# POWER.net
KiCad netlist of a schematic drawn in Altium Designer
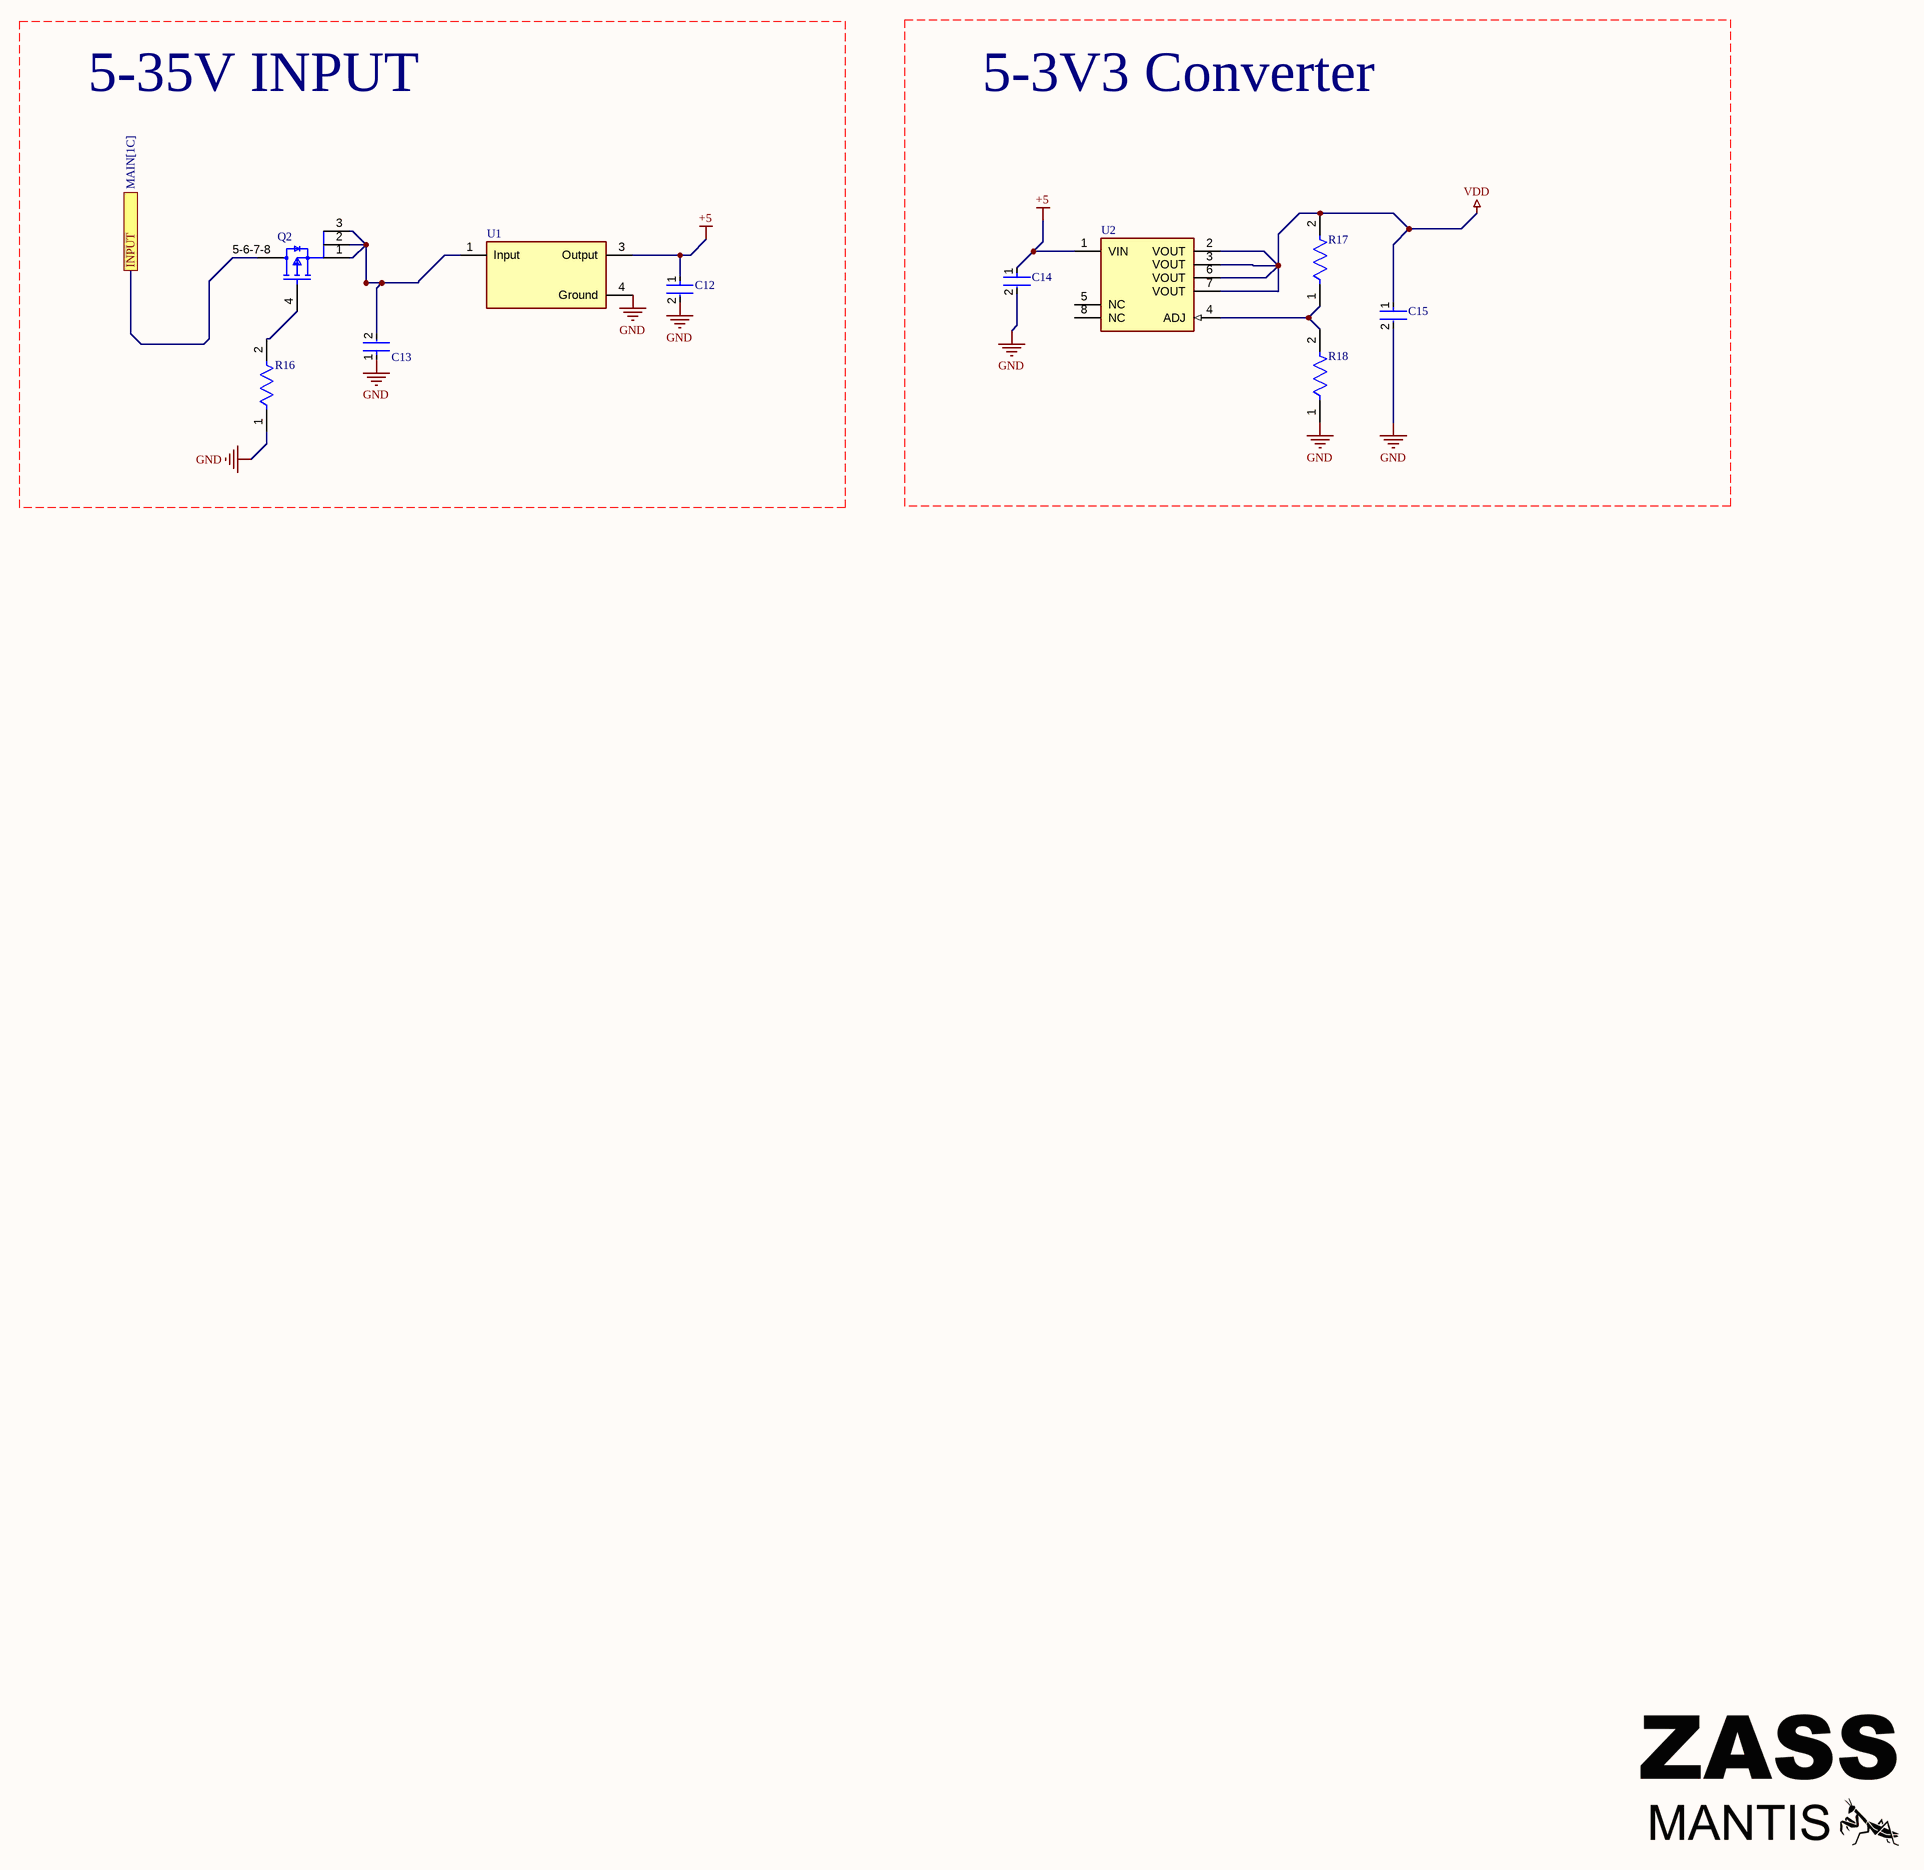
[diagram p0: POWER.SchDoc]

(export (version "E")
  (design (tool "Eeschema 10.0.6"))
  (components
    (comp (ref "C12")
      (value "CC0805KRX7R5BB104")
      (footprint "FP-CC0805-EA-MFG")
      (description "CAP CER X7R 0805")
      (libsource (lib "Altium Content Vault") (part "b4654b650e69147ec39a6b967a45e02"))
    )
    (comp (ref "C13")
      (value "C0805C104K5RACTU")
      (footprint "FP-C0805C-DN-MFG")
      (description "CAP CER 0.1UF 50V X7R 0805")
      (fields
        (field (name "MANUFACTURER") "KEMET")
        (field (name "OCTOPART") "https://octopart.com/c0805c104k5ractu-kemet-143926")
      )
      (libsource (lib "Altium Content Vault") (part "b4654b650e69147ec39a6b967a45e02"))
    )
    (comp (ref "C14")
      (value "CC0805KRX7R5BB104")
      (footprint "FP-CC0805-EA-MFG")
      (description "CAP CER X7R 0805")
      (libsource (lib "Altium Content Vault") (part "b4654b650e69147ec39a6b967a45e02"))
    )
    (comp (ref "C15")
      (value "CC0805KRX7R5BB104")
      (footprint "FP-CC0805-EA-MFG")
      (description "CAP CER X7R 0805")
      (libsource (lib "Altium Content Vault") (part "b4654b650e69147ec39a6b967a45e02"))
    )
    (comp (ref "Q2")
      (value "SI7113ADN-T1-GE3")
      (footprint "FP-S16-2667-SINGLE-MFG")
      (description "MOSFET P-CH 100V 10.8A 1212-8")
      (fields
        (field (name "MANUFACTURER") "Vishay")
        (field (name "OCTOPART") "https://octopart.com/si7113adn-t1-ge3-vishay-88182558")
      )
      (libsource (lib "Altium Content Vault") (part "a2b2833ae26e75c929b926ecaf5219e"))
    )
    (comp (ref "R16")
      (value "CRGCQ0603F1K2")
      (footprint "FP-CRGCQ0603-IPC_C")
      (description "CRGCQ 0603 1K2 1%")
      (fields
        (field (name "OCTOPART") "https://octopart.com/crgcq0603f1k2-te+connectivity-91018051")
        (field (name "MANUFACTURER") "TE Connectivity")
      )
      (libsource (lib "Altium Content Vault") (part "1029c3af85768c4190bb7ad29bc67b5"))
    )
    (comp (ref "R17")
      (value "CRGCQ0603F1K2")
      (footprint "FP-CRGCQ0603-IPC_C")
      (description "CRGCQ 0603 1K2 1%")
      (fields
        (field (name "OCTOPART") "https://octopart.com/crgcq0603f1k2-te+connectivity-91018051")
        (field (name "MANUFACTURER") "TE Connectivity")
      )
      (libsource (lib "Altium Content Vault") (part "1029c3af85768c4190bb7ad29bc67b5"))
    )
    (comp (ref "R18")
      (value "RC3216J202CS")
      (footprint "FP-RC3216-IPC_A")
      (description "Res Thick Film 1206 2kΩ 5% 0.25W ±100ppm/°C Molded SMD T/R")
      (fields (field (name "TOLERANCE") "5%"))
      (libsource (lib "Altium Content Vault") (part "1029c3af85768c4190bb7ad29bc67b5"))
    )
    (comp (ref "U1")
      (value "MC7805CDTRKG")
      (footprint "FP-369C-MFG")
      (description "IC REG LINEAR 5V 1A DPAK")
      (libsource (lib "Altium Content Vault") (part "10ca12a7ef27ecffb14ba267b90e28b"))
    )
    (comp (ref "U2")
      (value "LM317LD13TR")
      (footprint "FP-SO-8-0016023-MFG")
      (description "IC REG LINEAR POS ADJ 100MA 8SO")
      (fields (field (name "TOLERANCE") "5%"))
      (libsource (lib "Altium Content Vault") (part "6ba05c69c1aa673c6635bf9cb6f78fb"))
    )
  )
  (nets
    (net (code "1") (name "+5") (class "Default")
      (node (ref "C12") (pin "1") (pinfunction "1_1") (pintype "passive"))
      (node (ref "C14") (pin "1") (pinfunction "1_1") (pintype "passive"))
      (node (ref "U1") (pin "3") (pinfunction "Output_3") (pintype "power_in"))
      (node (ref "U2") (pin "1") (pinfunction "VIN_1") (pintype "power_in"))
    )
    (net (code "2") (name "/INPUT") (class "Default")
      (node (ref "Q2") (pin "5-6-7-8") (pinfunction "D_5-6-7-8") (pintype "passive"))
    )
    (net (code "3") (name "GND") (class "Default")
      (node (ref "C12") (pin "2") (pinfunction "2_2") (pintype "passive"))
      (node (ref "C13") (pin "1") (pinfunction "1_1") (pintype "passive"))
      (node (ref "C14") (pin "2") (pinfunction "2_2") (pintype "passive"))
      (node (ref "C15") (pin "2") (pinfunction "2_2") (pintype "passive"))
      (node (ref "R16") (pin "1") (pinfunction "1_1") (pintype "passive"))
      (node (ref "R18") (pin "1") (pinfunction "1_1") (pintype "passive"))
      (node (ref "U1") (pin "4") (pinfunction "Ground_4") (pintype "power_in"))
    )
    (net (code "4") (name "Net-(Q2-G)") (class "Default")
      (node (ref "Q2") (pin "4") (pinfunction "G_4") (pintype "passive"))
      (node (ref "R16") (pin "2") (pinfunction "2_2") (pintype "passive"))
    )
    (net (code "5") (name "Net-(U1-Input)") (class "Default")
      (node (ref "C13") (pin "2") (pinfunction "2_2") (pintype "passive"))
      (node (ref "Q2") (pin "1") (pinfunction "S_1") (pintype "passive"))
      (node (ref "Q2") (pin "2") (pinfunction "S_2") (pintype "passive"))
      (node (ref "Q2") (pin "3") (pinfunction "S_3") (pintype "passive"))
      (node (ref "U1") (pin "1") (pinfunction "Input_1") (pintype "power_in"))
    )
    (net (code "6") (name "Net-(U2-ADJ)") (class "Default")
      (node (ref "R17") (pin "1") (pinfunction "1_1") (pintype "passive"))
      (node (ref "R18") (pin "2") (pinfunction "2_2") (pintype "passive"))
      (node (ref "U2") (pin "4") (pinfunction "ADJ_4") (pintype "input"))
    )
    (net (code "7") (name "VDD") (class "Default")
      (node (ref "C15") (pin "1") (pinfunction "1_1") (pintype "passive"))
      (node (ref "R17") (pin "2") (pinfunction "2_2") (pintype "passive"))
      (node (ref "U2") (pin "2") (pinfunction "VOUT_2") (pintype "power_in"))
      (node (ref "U2") (pin "3") (pinfunction "VOUT_3") (pintype "power_in"))
      (node (ref "U2") (pin "6") (pinfunction "VOUT_6") (pintype "power_in"))
      (node (ref "U2") (pin "7") (pinfunction "VOUT_7") (pintype "power_in"))
    )
    (net (code "8") (name "unconnected-(U2-NC-Pad5)") (class "Default")
      (node (ref "U2") (pin "5") (pinfunction "NC_5") (pintype "passive"))
    )
    (net (code "9") (name "unconnected-(U2-NC-Pad8)") (class "Default")
      (node (ref "U2") (pin "8") (pinfunction "NC_8") (pintype "passive"))
    )
  )
)
